# dimmer_circuit.net
KiCad netlist of a schematic drawn in EAGLE
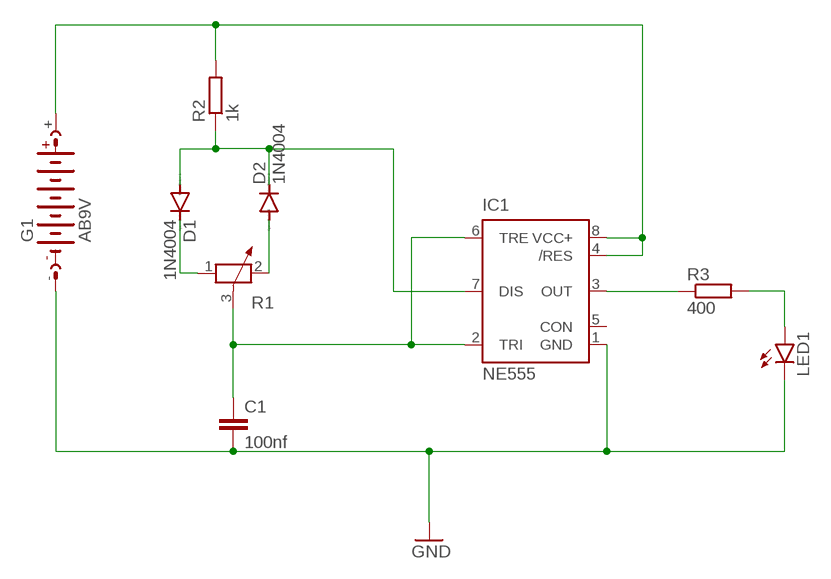
[diagram p0: schematic, sheet 1]

(export (version "E")
  (design (tool "Eeschema 10.0.6"))
  (components
    (comp (ref "C1")
      (value "100nf")
      (footprint "eagle-import:C025-025X050")
      (libsource (lib "eagle-import") (part "C-EU025-025X050"))
    )
    (comp (ref "D1")
      (value "1N4004")
      (footprint "eagle-import:DO41-10")
      (libsource (lib "eagle-import") (part "1N4004"))
    )
    (comp (ref "D2")
      (value "1N4004")
      (footprint "eagle-import:DO41-10")
      (libsource (lib "eagle-import") (part "1N4004"))
    )
    (comp (ref "G1")
      (value "AB9V")
      (footprint "eagle-import:AB9V")
      (libsource (lib "eagle-import") (part "AB9V"))
    )
    (comp (ref "IC1")
      (value "NE555")
      (footprint "eagle-import:DIL-08")
      (fields (field (name "MF") "Arrow Electronics") (field (name "MPN") "NE555N"))
      (libsource (lib "eagle-import") (part "NE555"))
    )
    (comp (ref "LED1")
      (value "LED5MM")
      (footprint "eagle-import:LED5MM")
      (libsource (lib "eagle-import") (part "LED5MM"))
    )
    (comp (ref "R1")
      (value "POTENTIOMETER_PT-10")
      (footprint "eagle-import:PT-10")
      (libsource (lib "eagle-import") (part "POTENTIOMETER_PT-10"))
    )
    (comp (ref "R2")
      (value "1k")
      (footprint "eagle-import:0204_7")
      (libsource (lib "eagle-import") (part "R-EU_0204/7"))
    )
    (comp (ref "R3")
      (value "400")
      (footprint "eagle-import:0204_7")
      (libsource (lib "eagle-import") (part "R-EU_0204/7"))
    )
  )
  (nets
    (net (code "1") (name "GND") (class "Default")
      (node (ref "C1") (pin "2") (pinfunction "2_2") (pintype "passive"))
      (node (ref "G1") (pin "-") (pinfunction "-_-") (pintype "passive"))
      (node (ref "IC1") (pin "1") (pinfunction "GND_1") (pintype "power_in"))
      (node (ref "LED1") (pin "K") (pinfunction "C_K") (pintype "passive"))
    )
    (net (code "2") (name "Net-(D1-PadC)") (class "Default")
      (node (ref "D1") (pin "C") (pinfunction "C_C") (pintype "passive"))
      (node (ref "R1") (pin "1") (pinfunction "1_1") (pintype "passive"))
    )
    (net (code "3") (name "Net-(D2-PadA)") (class "Default")
      (node (ref "D2") (pin "A") (pinfunction "A_A") (pintype "passive"))
      (node (ref "R1") (pin "2") (pinfunction "2_2") (pintype "passive"))
    )
    (net (code "4") (name "Net-(IC1-DIS)") (class "Default")
      (node (ref "D1") (pin "A") (pinfunction "A_A") (pintype "passive"))
      (node (ref "D2") (pin "C") (pinfunction "C_C") (pintype "passive"))
      (node (ref "IC1") (pin "7") (pinfunction "DIS_7") (pintype "input"))
      (node (ref "R2") (pin "1") (pinfunction "1_1") (pintype "passive"))
    )
    (net (code "5") (name "Net-(IC1-OUT)") (class "Default")
      (node (ref "IC1") (pin "3") (pinfunction "OUT_3") (pintype "output"))
      (node (ref "R3") (pin "1") (pinfunction "1_1") (pintype "passive"))
    )
    (net (code "6") (name "Net-(IC1-TRE)") (class "Default")
      (node (ref "C1") (pin "1") (pinfunction "1_1") (pintype "passive"))
      (node (ref "IC1") (pin "2") (pinfunction "TRI_2") (pintype "input"))
      (node (ref "IC1") (pin "6") (pinfunction "TRE_6") (pintype "input"))
      (node (ref "R1") (pin "3") (pinfunction "3_3") (pintype "passive"))
    )
    (net (code "7") (name "Net-(IC1-VCC+)") (class "Default")
      (node (ref "G1") (pin "+") (pinfunction "+_+") (pintype "passive"))
      (node (ref "IC1") (pin "4") (pinfunction "/RES_4") (pintype "input"))
      (node (ref "IC1") (pin "8") (pinfunction "VCC+_8") (pintype "power_in"))
      (node (ref "R2") (pin "2") (pinfunction "2_2") (pintype "passive"))
    )
    (net (code "8") (name "Net-(LED1-PadA)") (class "Default")
      (node (ref "LED1") (pin "A") (pinfunction "A_A") (pintype "passive"))
      (node (ref "R3") (pin "2") (pinfunction "2_2") (pintype "passive"))
    )
    (net (code "9") (name "unconnected-(IC1-CON-Pad5)") (class "Default")
      (node (ref "IC1") (pin "5") (pinfunction "CON_5") (pintype "input"))
    )
  )
)
